# Motor_Drivers.net
KiCad netlist of a schematic drawn in Altium Designer
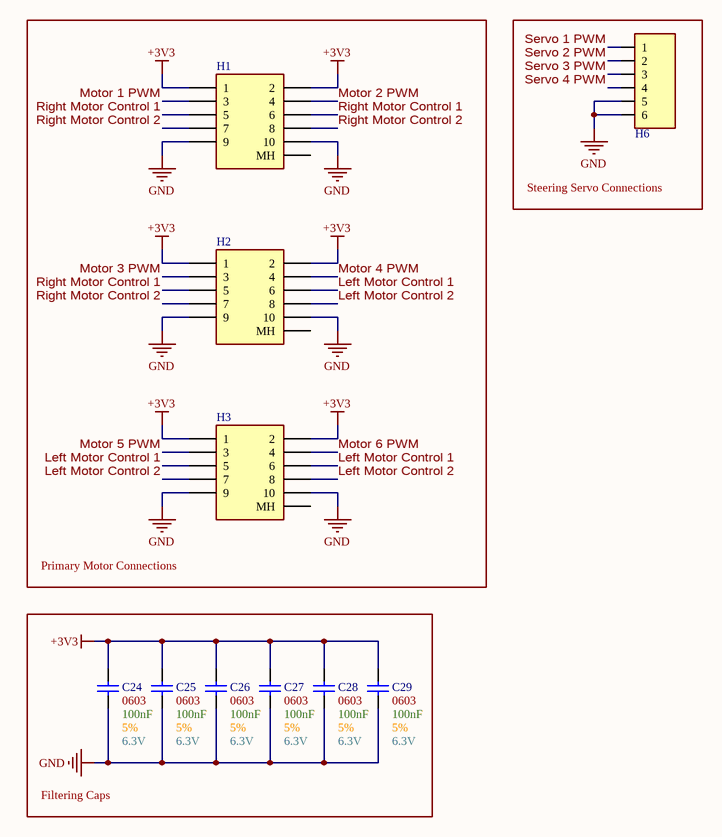
[diagram p0: Motor Drivers.SchDoc]

(export (version "E")
  (design (tool "Eeschema 10.0.6"))
  (components
    (comp (ref "C24")
      (value "[Cap] SMD Nonpolarized")
      (footprint "[Cap] SMD 0603")
      (fields
        (field (name "SIZE PACKAGE") "0603")
        (field (name "CAPACITANCE") "100nF")
        (field (name "VOLTAGE") "6.3V")
        (field (name "TOLERANCE") "5%")
      )
      (libsource (lib "RADM Components") (part "[Cap] SMD Nonpolarized"))
    )
    (comp (ref "C25")
      (value "[Cap] SMD Nonpolarized")
      (footprint "[Cap] SMD 0603")
      (fields
        (field (name "SIZE PACKAGE") "0603")
        (field (name "CAPACITANCE") "100nF")
        (field (name "VOLTAGE") "6.3V")
        (field (name "TOLERANCE") "5%")
      )
      (libsource (lib "RADM Components") (part "[Cap] SMD Nonpolarized"))
    )
    (comp (ref "C26")
      (value "[Cap] SMD Nonpolarized")
      (footprint "[Cap] SMD 0603")
      (fields
        (field (name "SIZE PACKAGE") "0603")
        (field (name "CAPACITANCE") "100nF")
        (field (name "VOLTAGE") "6.3V")
        (field (name "TOLERANCE") "5%")
      )
      (libsource (lib "RADM Components") (part "[Cap] SMD Nonpolarized"))
    )
    (comp (ref "C27")
      (value "[Cap] SMD Nonpolarized")
      (footprint "[Cap] SMD 0603")
      (fields
        (field (name "SIZE PACKAGE") "0603")
        (field (name "CAPACITANCE") "100nF")
        (field (name "VOLTAGE") "6.3V")
        (field (name "TOLERANCE") "5%")
      )
      (libsource (lib "RADM Components") (part "[Cap] SMD Nonpolarized"))
    )
    (comp (ref "C28")
      (value "[Cap] SMD Nonpolarized")
      (footprint "[Cap] SMD 0603")
      (fields
        (field (name "SIZE PACKAGE") "0603")
        (field (name "CAPACITANCE") "100nF")
        (field (name "VOLTAGE") "6.3V")
        (field (name "TOLERANCE") "5%")
      )
      (libsource (lib "RADM Components") (part "[Cap] SMD Nonpolarized"))
    )
    (comp (ref "C29")
      (value "[Cap] SMD Nonpolarized")
      (footprint "[Cap] SMD 0603")
      (fields
        (field (name "SIZE PACKAGE") "0603")
        (field (name "CAPACITANCE") "100nF")
        (field (name "VOLTAGE") "6.3V")
        (field (name "TOLERANCE") "5%")
      )
      (libsource (lib "RADM Components") (part "[Cap] SMD Nonpolarized"))
    )
    (comp (ref "H1")
      (value "[Header] Shrouded 2x5 SMD")
      (footprint "[Header] Shrouded 2x5 SMD")
      (libsource (lib "RADM Connectors") (part "[Header] Shrouded 2x5 SMD"))
    )
    (comp (ref "H2")
      (value "[Header] Shrouded 2x5 SMD")
      (footprint "[Header] Shrouded 2x5 SMD")
      (libsource (lib "RADM Connectors") (part "[Header] Shrouded 2x5 SMD"))
    )
    (comp (ref "H3")
      (value "[Header] Shrouded 2x5 SMD")
      (footprint "[Header] Shrouded 2x5 SMD")
      (libsource (lib "RADM Connectors") (part "[Header] Shrouded 2x5 SMD"))
    )
    (comp (ref "H6")
      (value "[Header] Shrouded 1x6 Male")
      (footprint "[Header] Shrouded 1x6 Male")
      (description "0705430005\r\nMates with 0050579406")
      (libsource (lib "RADM Connectors") (part "[Header] Shrouded 1x6 Male"))
    )
  )
  (nets
    (net (code "1") (name "+3V3") (class "Default")
      (node (ref "C24") (pin "2") (pinfunction "2_2") (pintype "passive"))
      (node (ref "C25") (pin "2") (pinfunction "2_2") (pintype "passive"))
      (node (ref "C26") (pin "2") (pinfunction "2_2") (pintype "passive"))
      (node (ref "C27") (pin "2") (pinfunction "2_2") (pintype "passive"))
      (node (ref "C28") (pin "2") (pinfunction "2_2") (pintype "passive"))
      (node (ref "C29") (pin "2") (pinfunction "2_2") (pintype "passive"))
      (node (ref "H1") (pin "1") (pinfunction "1_1") (pintype "passive"))
      (node (ref "H1") (pin "2") (pinfunction "2_2") (pintype "passive"))
      (node (ref "H2") (pin "1") (pinfunction "1_1") (pintype "passive"))
      (node (ref "H2") (pin "2") (pinfunction "2_2") (pintype "passive"))
      (node (ref "H3") (pin "1") (pinfunction "1_1") (pintype "passive"))
      (node (ref "H3") (pin "2") (pinfunction "2_2") (pintype "passive"))
    )
    (net (code "2") (name "/Left Motor Control 1") (class "Default")
      (node (ref "H2") (pin "6") (pinfunction "6_6") (pintype "passive"))
      (node (ref "H3") (pin "5") (pinfunction "5_5") (pintype "passive"))
      (node (ref "H3") (pin "6") (pinfunction "6_6") (pintype "passive"))
    )
    (net (code "3") (name "/Left Motor Control 2") (class "Default")
      (node (ref "H2") (pin "8") (pinfunction "8_8") (pintype "passive"))
      (node (ref "H3") (pin "7") (pinfunction "7_7") (pintype "passive"))
      (node (ref "H3") (pin "8") (pinfunction "8_8") (pintype "passive"))
    )
    (net (code "4") (name "/Motor 1 PWM") (class "Default")
      (node (ref "H1") (pin "3") (pinfunction "3_3") (pintype "passive"))
    )
    (net (code "5") (name "/Motor 2 PWM") (class "Default")
      (node (ref "H1") (pin "4") (pinfunction "4_4") (pintype "passive"))
    )
    (net (code "6") (name "/Motor 3 PWM") (class "Default")
      (node (ref "H2") (pin "3") (pinfunction "3_3") (pintype "passive"))
    )
    (net (code "7") (name "/Motor 4 PWM") (class "Default")
      (node (ref "H2") (pin "4") (pinfunction "4_4") (pintype "passive"))
    )
    (net (code "8") (name "/Motor 5 PWM") (class "Default")
      (node (ref "H3") (pin "3") (pinfunction "3_3") (pintype "passive"))
    )
    (net (code "9") (name "/Motor 6 PWM") (class "Default")
      (node (ref "H3") (pin "4") (pinfunction "4_4") (pintype "passive"))
    )
    (net (code "10") (name "/Right Motor Control 1") (class "Default")
      (node (ref "H1") (pin "5") (pinfunction "5_5") (pintype "passive"))
      (node (ref "H1") (pin "6") (pinfunction "6_6") (pintype "passive"))
      (node (ref "H2") (pin "5") (pinfunction "5_5") (pintype "passive"))
    )
    (net (code "11") (name "/Right Motor Control 2") (class "Default")
      (node (ref "H1") (pin "7") (pinfunction "7_7") (pintype "passive"))
      (node (ref "H1") (pin "8") (pinfunction "8_8") (pintype "passive"))
      (node (ref "H2") (pin "7") (pinfunction "7_7") (pintype "passive"))
    )
    (net (code "12") (name "/Servo 1 PWM") (class "Default")
      (node (ref "H6") (pin "1") (pinfunction "1_1") (pintype "passive"))
    )
    (net (code "13") (name "/Servo 2 PWM") (class "Default")
      (node (ref "H6") (pin "2") (pinfunction "2_2") (pintype "passive"))
    )
    (net (code "14") (name "/Servo 3 PWM") (class "Default")
      (node (ref "H6") (pin "3") (pinfunction "3_3") (pintype "passive"))
    )
    (net (code "15") (name "/Servo 4 PWM") (class "Default")
      (node (ref "H6") (pin "4") (pinfunction "4_4") (pintype "passive"))
    )
    (net (code "16") (name "GND") (class "Default")
      (node (ref "C24") (pin "1") (pinfunction "1_1") (pintype "passive"))
      (node (ref "C25") (pin "1") (pinfunction "1_1") (pintype "passive"))
      (node (ref "C26") (pin "1") (pinfunction "1_1") (pintype "passive"))
      (node (ref "C27") (pin "1") (pinfunction "1_1") (pintype "passive"))
      (node (ref "C28") (pin "1") (pinfunction "1_1") (pintype "passive"))
      (node (ref "C29") (pin "1") (pinfunction "1_1") (pintype "passive"))
      (node (ref "H1") (pin "10") (pinfunction "10_10") (pintype "passive"))
      (node (ref "H1") (pin "9") (pinfunction "9_9") (pintype "passive"))
      (node (ref "H2") (pin "10") (pinfunction "10_10") (pintype "passive"))
      (node (ref "H2") (pin "9") (pinfunction "9_9") (pintype "passive"))
      (node (ref "H3") (pin "10") (pinfunction "10_10") (pintype "passive"))
      (node (ref "H3") (pin "9") (pinfunction "9_9") (pintype "passive"))
      (node (ref "H6") (pin "5") (pinfunction "5_5") (pintype "passive"))
      (node (ref "H6") (pin "6") (pinfunction "6_6") (pintype "passive"))
    )
    (net (code "17") (name "unconnected-(H1-MH-PadX)") (class "Default")
      (node (ref "H1") (pin "X") (pinfunction "MH_X") (pintype "passive"))
    )
    (net (code "18") (name "unconnected-(H2-MH-PadX)") (class "Default")
      (node (ref "H2") (pin "X") (pinfunction "MH_X") (pintype "passive"))
    )
    (net (code "19") (name "unconnected-(H3-MH-PadX)") (class "Default")
      (node (ref "H3") (pin "X") (pinfunction "MH_X") (pintype "passive"))
    )
  )
)
